# wire.net
KiCad netlist of a schematic drawn in EAGLE
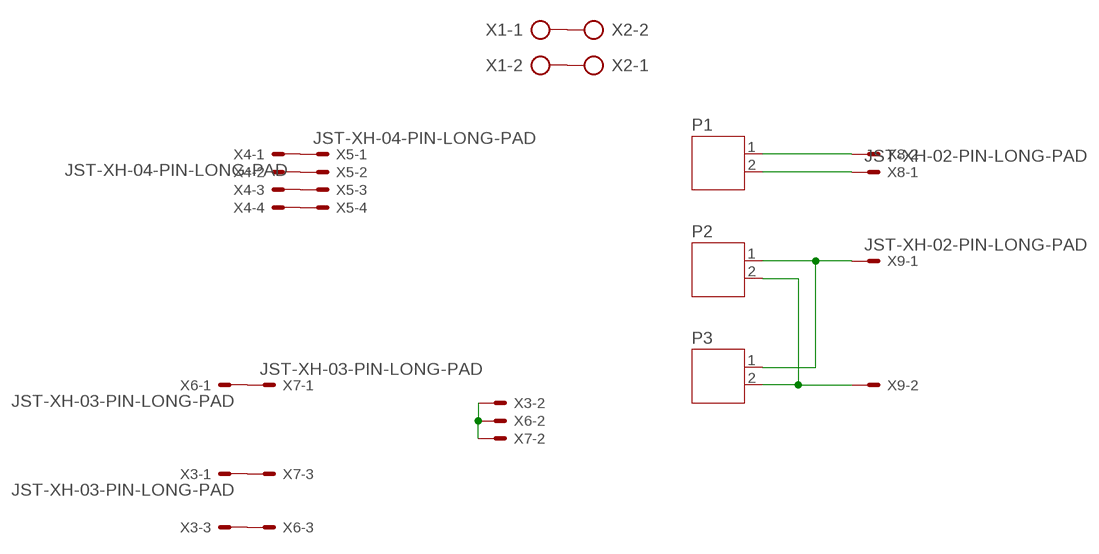
[diagram p0: schematic, sheet 1]

(export (version "E")
  (design (tool "Eeschema 10.0.6"))
  (components
    (comp (ref "P1")
      (value "JST-PH2")
      (footprint "eagle-import:JST-PH2")
      (libsource (lib "eagle-import") (part "JST-PH2"))
    )
    (comp (ref "P2")
      (value "JST-PH2")
      (footprint "eagle-import:JST-PH2")
      (libsource (lib "eagle-import") (part "JST-PH2"))
    )
    (comp (ref "P3")
      (value "JST-PH2")
      (footprint "eagle-import:JST-PH2")
      (libsource (lib "eagle-import") (part "JST-PH2"))
    )
    (comp (ref "X1")
      (value "AK500/2")
      (footprint "eagle-import:AK500_2")
      (libsource (lib "eagle-import") (part "AK500/2"))
    )
    (comp (ref "X2")
      (value "AK500/2")
      (footprint "eagle-import:AK500_2")
      (libsource (lib "eagle-import") (part "AK500/2"))
    )
    (comp (ref "X3")
      (value "JST-XH-03-PIN-LONG-PAD")
      (footprint "eagle-import:JST-XH-03-PACKAGE-LONG-PAD")
      (libsource (lib "eagle-import") (part "JST-XH-03-PIN-LONG-PAD"))
    )
    (comp (ref "X4")
      (value "JST-XH-04-PIN-LONG-PAD")
      (footprint "eagle-import:JST-XH-04-PACKAGE-LONG-PAD")
      (libsource (lib "eagle-import") (part "JST-XH-04-PIN-LONG-PAD"))
    )
    (comp (ref "X5")
      (value "JST-XH-04-PIN-LONG-PAD")
      (footprint "eagle-import:JST-XH-04-PACKAGE-LONG-PAD")
      (libsource (lib "eagle-import") (part "JST-XH-04-PIN-LONG-PAD"))
    )
    (comp (ref "X6")
      (value "JST-XH-03-PIN-LONG-PAD")
      (footprint "eagle-import:JST-XH-03-PACKAGE-LONG-PAD")
      (libsource (lib "eagle-import") (part "JST-XH-03-PIN-LONG-PAD"))
    )
    (comp (ref "X7")
      (value "JST-XH-03-PIN-LONG-PAD")
      (footprint "eagle-import:JST-XH-03-PACKAGE-LONG-PAD")
      (libsource (lib "eagle-import") (part "JST-XH-03-PIN-LONG-PAD"))
    )
    (comp (ref "X8")
      (value "JST-XH-02-PIN-LONG-PAD")
      (footprint "eagle-import:JST-XH-02-PACKAGE-LONG-PAD")
      (libsource (lib "eagle-import") (part "JST-XH-02-PIN-LONG-PAD"))
    )
    (comp (ref "X9")
      (value "JST-XH-02-PIN-LONG-PAD")
      (footprint "eagle-import:JST-XH-02-PACKAGE-LONG-PAD")
      (libsource (lib "eagle-import") (part "JST-XH-02-PIN-LONG-PAD"))
    )
  )
  (nets
    (net (code "1") (name "Net-(X1A-KL)") (class "Default")
      (node (ref "X1") (pin "1") (pinfunction "KL_1") (pintype "passive"))
      (node (ref "X2") (pin "2") (pinfunction "KL_2") (pintype "passive"))
    )
    (net (code "2") (name "Net-(X1B-KL)") (class "Default")
      (node (ref "X1") (pin "2") (pinfunction "KL_2") (pintype "passive"))
      (node (ref "X2") (pin "1") (pinfunction "KL_1") (pintype "passive"))
    )
    (net (code "3") (name "Net-(X3A-S)") (class "Default")
      (node (ref "X3") (pin "1") (pinfunction "S_1") (pintype "passive"))
      (node (ref "X7") (pin "3") (pinfunction "S_3") (pintype "passive"))
    )
    (net (code "4") (name "Net-(X3B-S)") (class "Default")
      (node (ref "X3") (pin "2") (pinfunction "S_2") (pintype "passive"))
      (node (ref "X6") (pin "2") (pinfunction "S_2") (pintype "passive"))
      (node (ref "X7") (pin "2") (pinfunction "S_2") (pintype "passive"))
    )
    (net (code "5") (name "Net-(X3C-S)") (class "Default")
      (node (ref "X3") (pin "3") (pinfunction "S_3") (pintype "passive"))
      (node (ref "X6") (pin "3") (pinfunction "S_3") (pintype "passive"))
    )
    (net (code "6") (name "Net-(X4A-S)") (class "Default")
      (node (ref "X4") (pin "1") (pinfunction "S_1") (pintype "passive"))
      (node (ref "X5") (pin "1") (pinfunction "S_1") (pintype "passive"))
    )
    (net (code "7") (name "Net-(X4B-S)") (class "Default")
      (node (ref "X4") (pin "2") (pinfunction "S_2") (pintype "passive"))
      (node (ref "X5") (pin "2") (pinfunction "S_2") (pintype "passive"))
    )
    (net (code "8") (name "Net-(X4C-S)") (class "Default")
      (node (ref "X4") (pin "3") (pinfunction "S_3") (pintype "passive"))
      (node (ref "X5") (pin "3") (pinfunction "S_3") (pintype "passive"))
    )
    (net (code "9") (name "Net-(X4D-S)") (class "Default")
      (node (ref "X4") (pin "4") (pinfunction "S_4") (pintype "passive"))
      (node (ref "X5") (pin "4") (pinfunction "S_4") (pintype "passive"))
    )
    (net (code "10") (name "Net-(X6A-S)") (class "Default")
      (node (ref "X6") (pin "1") (pinfunction "S_1") (pintype "passive"))
      (node (ref "X7") (pin "1") (pinfunction "S_1") (pintype "passive"))
    )
    (net (code "11") (name "Net-(X8A-S)") (class "Default")
      (node (ref "P1") (pin "2") (pinfunction "2_2") (pintype "passive"))
      (node (ref "X8") (pin "1") (pinfunction "S_1") (pintype "passive"))
    )
    (net (code "12") (name "Net-(X8B-S)") (class "Default")
      (node (ref "P1") (pin "1") (pinfunction "1_1") (pintype "passive"))
      (node (ref "X8") (pin "2") (pinfunction "S_2") (pintype "passive"))
    )
    (net (code "13") (name "Net-(X9A-S)") (class "Default")
      (node (ref "P2") (pin "1") (pinfunction "1_1") (pintype "passive"))
      (node (ref "P3") (pin "1") (pinfunction "1_1") (pintype "passive"))
      (node (ref "X9") (pin "1") (pinfunction "S_1") (pintype "passive"))
    )
    (net (code "14") (name "Net-(X9B-S)") (class "Default")
      (node (ref "P2") (pin "2") (pinfunction "2_2") (pintype "passive"))
      (node (ref "P3") (pin "2") (pinfunction "2_2") (pintype "passive"))
      (node (ref "X9") (pin "2") (pinfunction "S_2") (pintype "passive"))
    )
  )
)
